# devboard_kw2xd_v2_1.net
KiCad netlist of a schematic drawn in EAGLE
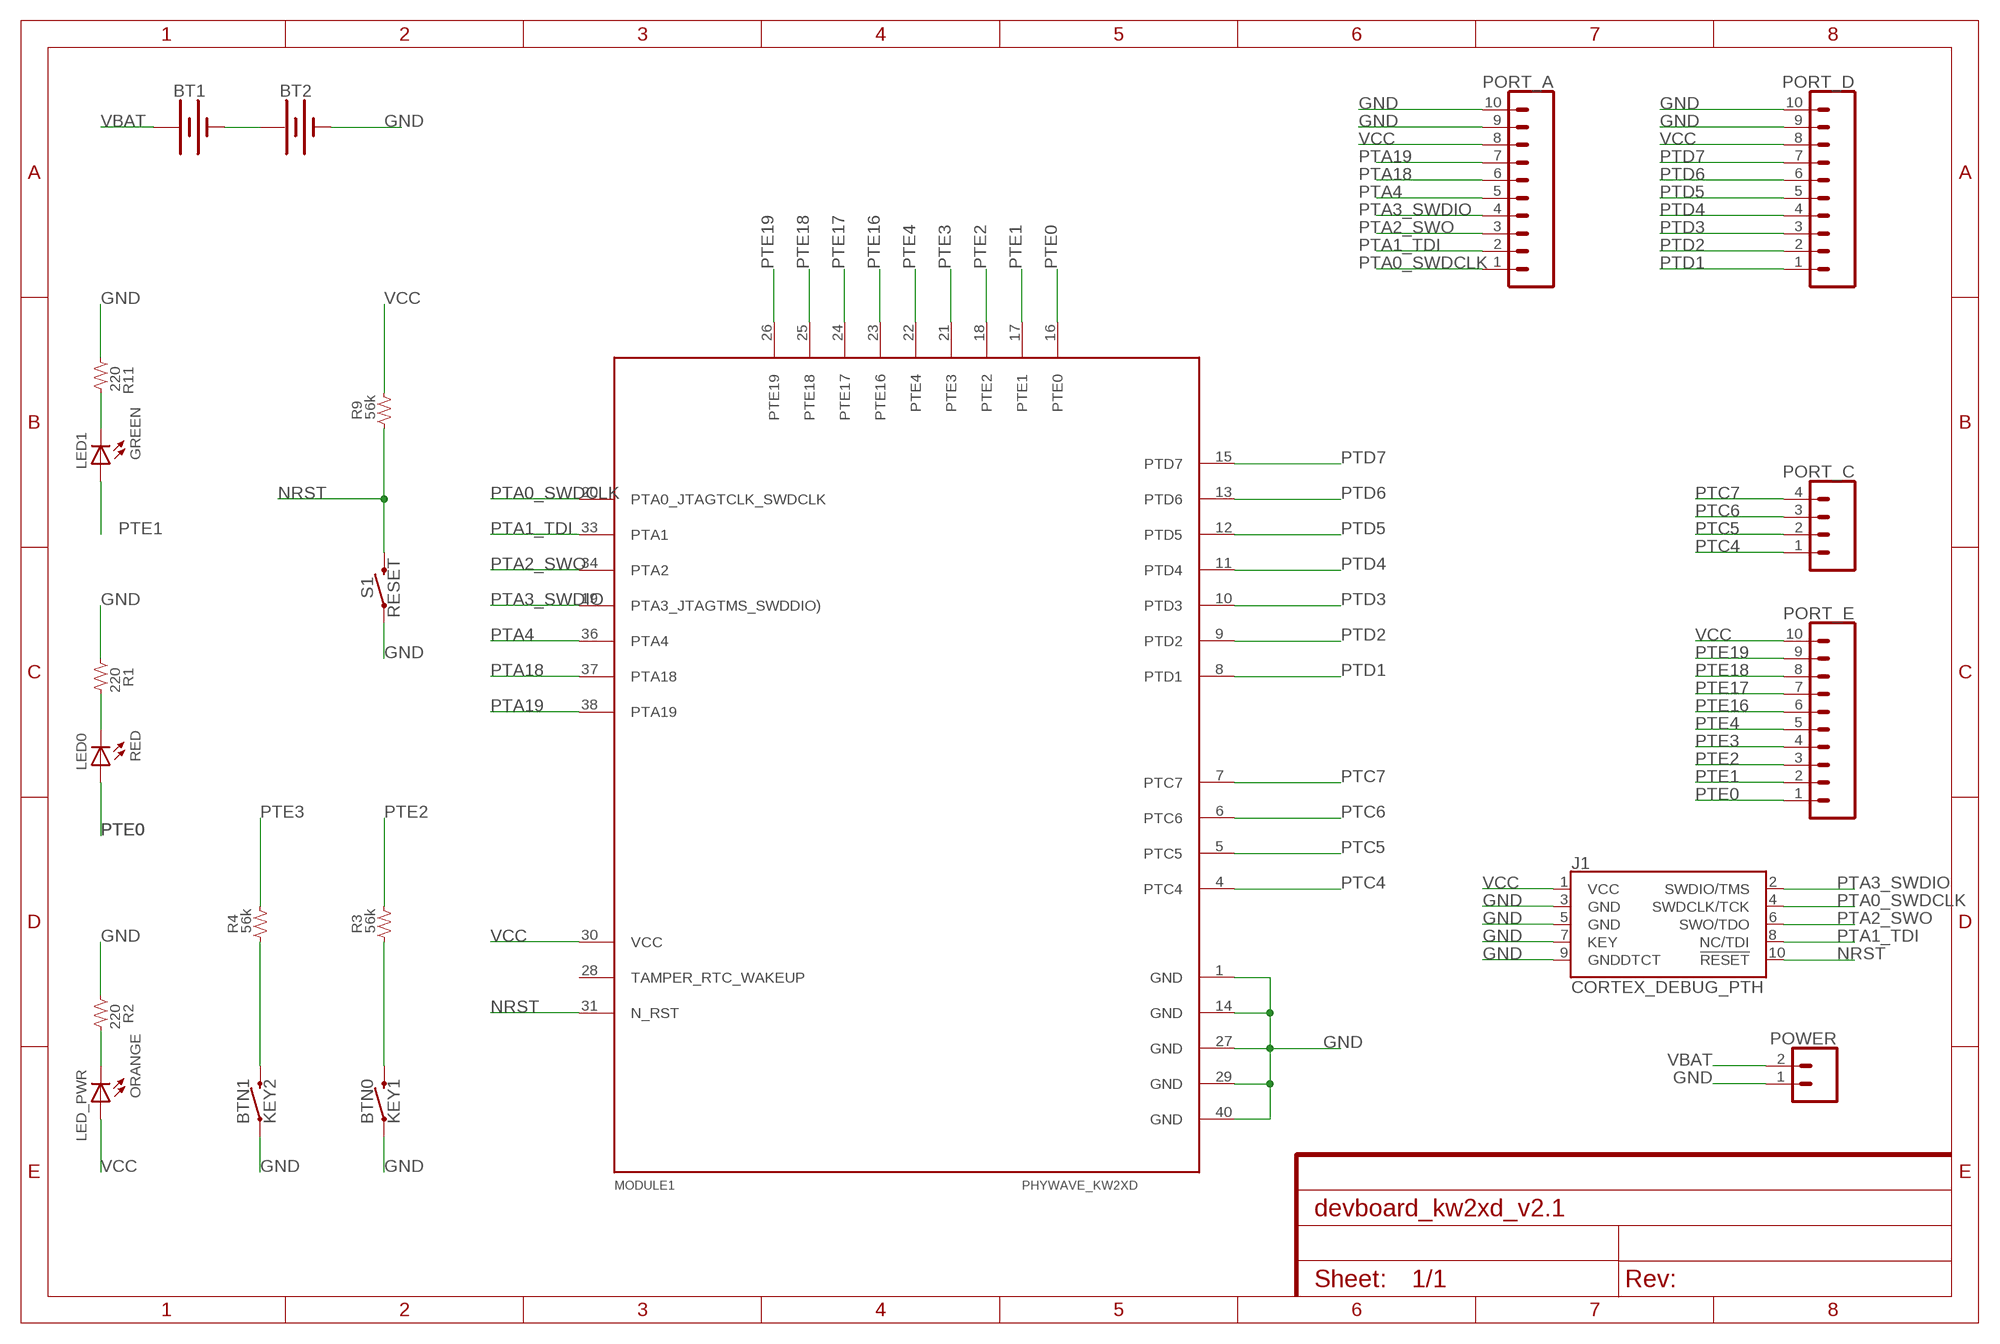
[diagram p0: schematic, sheet 1]

(export (version "E")
  (design (tool "Eeschema 10.0.6"))
  (components
    (comp (ref "BT1")
      (value "BATTERY-AAA")
      (footprint "eagle-import:BATTERY-AAA")
      (libsource (lib "eagle-import") (part "BATTERY-AAA"))
    )
    (comp (ref "BT2")
      (value "BATTERY-AAA")
      (footprint "eagle-import:BATTERY-AAA")
      (libsource (lib "eagle-import") (part "BATTERY-AAA"))
    )
    (comp (ref "BTN0")
      (value "KEY1")
      (footprint "eagle-import:TACTILE_SWITCH_SMD_4.6X2.8MM")
      (libsource (lib "eagle-import") (part "MOMENTARY-SWITCH-SPST-SMD-4.6X2.8MM"))
    )
    (comp (ref "BTN1")
      (value "KEY2")
      (footprint "eagle-import:TACTILE_SWITCH_SMD_4.6X2.8MM")
      (libsource (lib "eagle-import") (part "MOMENTARY-SWITCH-SPST-SMD-4.6X2.8MM"))
    )
    (comp (ref "J1")
      (value "CORTEX_DEBUG_PTH")
      (footprint "eagle-import:2X5-PTH-1.27MM")
      (libsource (lib "eagle-import") (part "CORTEX_DEBUG_PTH"))
    )
    (comp (ref "LED0")
      (value "RED")
      (footprint "eagle-import:LED0603")
      (libsource (lib "eagle-import") (part "LED-0603"))
    )
    (comp (ref "LED1")
      (value "GREEN")
      (footprint "eagle-import:LED0603")
      (libsource (lib "eagle-import") (part "LED-0603"))
    )
    (comp (ref "LED_PWR")
      (value "ORANGE")
      (footprint "eagle-import:LED0603")
      (libsource (lib "eagle-import") (part "LED-0603"))
    )
    (comp (ref "MODULE1")
      (value "PHYWAVE_KW2XD")
      (footprint "eagle-import:PHYWAVE_KW2XD")
      (libsource (lib "eagle-import") (part "PHYWAVE_KW2XD"))
    )
    (comp (ref "PORT_A")
      (value "CONN_10\"")
      (footprint "eagle-import:1X10")
      (libsource (lib "eagle-import") (part "CONN_10{dblquote}"))
    )
    (comp (ref "PORT_C")
      (value "CONN_04")
      (footprint "eagle-import:1X04")
      (libsource (lib "eagle-import") (part "CONN_04"))
    )
    (comp (ref "PORT_D")
      (value "CONN_10\"")
      (footprint "eagle-import:1X10")
      (libsource (lib "eagle-import") (part "CONN_10{dblquote}"))
    )
    (comp (ref "PORT_E")
      (value "CONN_10\"")
      (footprint "eagle-import:1X10")
      (libsource (lib "eagle-import") (part "CONN_10{dblquote}"))
    )
    (comp (ref "POWER")
      (value "CONN_02")
      (footprint "eagle-import:1X02")
      (libsource (lib "eagle-import") (part "CONN_02"))
    )
    (comp (ref "R1")
      (value "220")
      (footprint "eagle-import:SMD0603")
      (libsource (lib "eagle-import") (part "R-0603"))
    )
    (comp (ref "R2")
      (value "220")
      (footprint "eagle-import:SMD0603")
      (libsource (lib "eagle-import") (part "R-0603"))
    )
    (comp (ref "R3")
      (value "56k")
      (footprint "eagle-import:SMD0603")
      (libsource (lib "eagle-import") (part "R-0603"))
    )
    (comp (ref "R4")
      (value "56k")
      (footprint "eagle-import:SMD0603")
      (libsource (lib "eagle-import") (part "R-0603"))
    )
    (comp (ref "R9")
      (value "56k")
      (footprint "eagle-import:SMD0603")
      (libsource (lib "eagle-import") (part "R-0603"))
    )
    (comp (ref "R11")
      (value "220")
      (footprint "eagle-import:SMD0603")
      (libsource (lib "eagle-import") (part "R-0603"))
    )
    (comp (ref "S1")
      (value "RESET")
      (footprint "eagle-import:TACTILE_SWITCH_SMD_4.6X2.8MM")
      (libsource (lib "eagle-import") (part "MOMENTARY-SWITCH-SPST-SMD-4.6X2.8MM"))
    )
  )
  (nets
    (net (code "1") (name "/GND") (class "Default")
      (node (ref "BT2") (pin "GND@1") (pinfunction "-_GND@1") (pintype "power_in"))
      (node (ref "BTN0") (pin "1") (pinfunction "1_1") (pintype "passive"))
      (node (ref "BTN0") (pin "2") (pinfunction "1_2") (pintype "passive"))
      (node (ref "BTN1") (pin "1") (pinfunction "1_1") (pintype "passive"))
      (node (ref "BTN1") (pin "2") (pinfunction "1_2") (pintype "passive"))
      (node (ref "J1") (pin "3") (pinfunction "GND_3") (pintype "bidirectional"))
      (node (ref "J1") (pin "5") (pinfunction "GND_5") (pintype "bidirectional"))
      (node (ref "J1") (pin "7") (pinfunction "KEY_7") (pintype "bidirectional"))
      (node (ref "J1") (pin "9") (pinfunction "GNDDTCT_9") (pintype "bidirectional"))
      (node (ref "MODULE1") (pin "1") (pinfunction "GND_1") (pintype "bidirectional"))
      (node (ref "MODULE1") (pin "14") (pinfunction "GND_14") (pintype "bidirectional"))
      (node (ref "MODULE1") (pin "27") (pinfunction "GND_27") (pintype "bidirectional"))
      (node (ref "MODULE1") (pin "29") (pinfunction "GND_29") (pintype "bidirectional"))
      (node (ref "MODULE1") (pin "40") (pinfunction "GND_40") (pintype "bidirectional"))
      (node (ref "PORT_A") (pin "10") (pinfunction "10_10") (pintype "passive"))
      (node (ref "PORT_A") (pin "9") (pinfunction "9_9") (pintype "passive"))
      (node (ref "PORT_D") (pin "10") (pinfunction "10_10") (pintype "passive"))
      (node (ref "PORT_D") (pin "9") (pinfunction "9_9") (pintype "passive"))
      (node (ref "POWER") (pin "1") (pinfunction "1_1") (pintype "passive"))
      (node (ref "R1") (pin "1") (pinfunction "1_1") (pintype "passive"))
      (node (ref "R11") (pin "1") (pinfunction "1_1") (pintype "passive"))
      (node (ref "R2") (pin "1") (pinfunction "1_1") (pintype "passive"))
      (node (ref "S1") (pin "1") (pinfunction "1_1") (pintype "passive"))
      (node (ref "S1") (pin "2") (pinfunction "1_2") (pintype "passive"))
    )
    (net (code "2") (name "/NRST") (class "Default")
      (node (ref "BTN0") (pin "3") (pinfunction "2_3") (pintype "passive"))
      (node (ref "BTN0") (pin "4") (pinfunction "2_4") (pintype "passive"))
      (node (ref "J1") (pin "10") (pinfunction "~{RESET}_10") (pintype "bidirectional"))
      (node (ref "MODULE1") (pin "31") (pinfunction "N_RST_31") (pintype "bidirectional"))
      (node (ref "R3") (pin "1") (pinfunction "1_1") (pintype "passive"))
      (node (ref "R9") (pin "1") (pinfunction "1_1") (pintype "passive"))
      (node (ref "S1") (pin "3") (pinfunction "2_3") (pintype "passive"))
      (node (ref "S1") (pin "4") (pinfunction "2_4") (pintype "passive"))
    )
    (net (code "3") (name "/PTA0_SWDCLK") (class "Default")
      (node (ref "J1") (pin "4") (pinfunction "SWDCLK/TCK_4") (pintype "bidirectional"))
      (node (ref "MODULE1") (pin "20") (pinfunction "PTA0_JTAGTCLK_SWDCLK_20") (pintype "bidirectional"))
      (node (ref "PORT_A") (pin "1") (pinfunction "1_1") (pintype "passive"))
    )
    (net (code "4") (name "/PTA1_TDI") (class "Default")
      (node (ref "J1") (pin "8") (pinfunction "NC/TDI_8") (pintype "bidirectional"))
      (node (ref "MODULE1") (pin "33") (pinfunction "PTA1_33") (pintype "bidirectional"))
      (node (ref "PORT_A") (pin "2") (pinfunction "2_2") (pintype "passive"))
    )
    (net (code "5") (name "/PTA2_SWO") (class "Default")
      (node (ref "J1") (pin "6") (pinfunction "SWO/TDO_6") (pintype "bidirectional"))
      (node (ref "MODULE1") (pin "34") (pinfunction "PTA2_34") (pintype "bidirectional"))
      (node (ref "PORT_A") (pin "3") (pinfunction "3_3") (pintype "passive"))
    )
    (net (code "6") (name "/PTA3_SWDIO") (class "Default")
      (node (ref "J1") (pin "2") (pinfunction "SWDIO/TMS_2") (pintype "bidirectional"))
      (node (ref "MODULE1") (pin "19") (pinfunction "PTA3_JTAGTMS_SWDDIO)_19") (pintype "bidirectional"))
      (node (ref "PORT_A") (pin "4") (pinfunction "4_4") (pintype "passive"))
    )
    (net (code "7") (name "/PTA4") (class "Default")
      (node (ref "MODULE1") (pin "36") (pinfunction "PTA4_36") (pintype "bidirectional"))
      (node (ref "PORT_A") (pin "5") (pinfunction "5_5") (pintype "passive"))
    )
    (net (code "8") (name "/PTA18") (class "Default")
      (node (ref "MODULE1") (pin "37") (pinfunction "PTA18_37") (pintype "bidirectional"))
      (node (ref "PORT_A") (pin "6") (pinfunction "6_6") (pintype "passive"))
    )
    (net (code "9") (name "/PTA19") (class "Default")
      (node (ref "MODULE1") (pin "38") (pinfunction "PTA19_38") (pintype "bidirectional"))
      (node (ref "PORT_A") (pin "7") (pinfunction "7_7") (pintype "passive"))
    )
    (net (code "10") (name "/PTC4") (class "Default")
      (node (ref "MODULE1") (pin "4") (pinfunction "PTC4_4") (pintype "bidirectional"))
      (node (ref "PORT_C") (pin "1") (pinfunction "1_1") (pintype "passive"))
    )
    (net (code "11") (name "/PTC5") (class "Default")
      (node (ref "MODULE1") (pin "5") (pinfunction "PTC5_5") (pintype "bidirectional"))
      (node (ref "PORT_C") (pin "2") (pinfunction "2_2") (pintype "passive"))
    )
    (net (code "12") (name "/PTC6") (class "Default")
      (node (ref "MODULE1") (pin "6") (pinfunction "PTC6_6") (pintype "bidirectional"))
      (node (ref "PORT_C") (pin "3") (pinfunction "3_3") (pintype "passive"))
    )
    (net (code "13") (name "/PTC7") (class "Default")
      (node (ref "MODULE1") (pin "7") (pinfunction "PTC7_7") (pintype "bidirectional"))
      (node (ref "PORT_C") (pin "4") (pinfunction "4_4") (pintype "passive"))
    )
    (net (code "14") (name "/PTD1") (class "Default")
      (node (ref "MODULE1") (pin "8") (pinfunction "PTD1_8") (pintype "bidirectional"))
      (node (ref "PORT_D") (pin "1") (pinfunction "1_1") (pintype "passive"))
    )
    (net (code "15") (name "/PTD2") (class "Default")
      (node (ref "MODULE1") (pin "9") (pinfunction "PTD2_9") (pintype "bidirectional"))
      (node (ref "PORT_D") (pin "2") (pinfunction "2_2") (pintype "passive"))
    )
    (net (code "16") (name "/PTD3") (class "Default")
      (node (ref "MODULE1") (pin "10") (pinfunction "PTD3_10") (pintype "bidirectional"))
      (node (ref "PORT_D") (pin "3") (pinfunction "3_3") (pintype "passive"))
    )
    (net (code "17") (name "/PTD4") (class "Default")
      (node (ref "MODULE1") (pin "11") (pinfunction "PTD4_11") (pintype "bidirectional"))
      (node (ref "PORT_D") (pin "4") (pinfunction "4_4") (pintype "passive"))
    )
    (net (code "18") (name "/PTD5") (class "Default")
      (node (ref "MODULE1") (pin "12") (pinfunction "PTD5_12") (pintype "bidirectional"))
      (node (ref "PORT_D") (pin "5") (pinfunction "5_5") (pintype "passive"))
    )
    (net (code "19") (name "/PTD6") (class "Default")
      (node (ref "MODULE1") (pin "13") (pinfunction "PTD6_13") (pintype "bidirectional"))
      (node (ref "PORT_D") (pin "6") (pinfunction "6_6") (pintype "passive"))
    )
    (net (code "20") (name "/PTD7") (class "Default")
      (node (ref "MODULE1") (pin "15") (pinfunction "PTD7_15") (pintype "bidirectional"))
      (node (ref "PORT_D") (pin "7") (pinfunction "7_7") (pintype "passive"))
    )
    (net (code "21") (name "/PTE0") (class "Default")
      (node (ref "LED0") (pin "A") (pinfunction "A_A") (pintype "passive"))
      (node (ref "MODULE1") (pin "16") (pinfunction "PTE0_16") (pintype "bidirectional"))
      (node (ref "PORT_E") (pin "1") (pinfunction "1_1") (pintype "passive"))
    )
    (net (code "22") (name "/PTE1") (class "Default")
      (node (ref "LED1") (pin "A") (pinfunction "A_A") (pintype "passive"))
      (node (ref "MODULE1") (pin "17") (pinfunction "PTE1_17") (pintype "bidirectional"))
      (node (ref "PORT_E") (pin "2") (pinfunction "2_2") (pintype "passive"))
    )
    (net (code "23") (name "/PTE2") (class "Default")
      (node (ref "MODULE1") (pin "18") (pinfunction "PTE2_18") (pintype "bidirectional"))
      (node (ref "PORT_E") (pin "3") (pinfunction "3_3") (pintype "passive"))
      (node (ref "R3") (pin "2") (pinfunction "2_2") (pintype "passive"))
    )
    (net (code "24") (name "/PTE3") (class "Default")
      (node (ref "MODULE1") (pin "21") (pinfunction "PTE3_21") (pintype "bidirectional"))
      (node (ref "PORT_E") (pin "4") (pinfunction "4_4") (pintype "passive"))
      (node (ref "R4") (pin "2") (pinfunction "2_2") (pintype "passive"))
    )
    (net (code "25") (name "/PTE4") (class "Default")
      (node (ref "MODULE1") (pin "22") (pinfunction "PTE4_22") (pintype "bidirectional"))
      (node (ref "PORT_E") (pin "5") (pinfunction "5_5") (pintype "passive"))
    )
    (net (code "26") (name "/PTE16") (class "Default")
      (node (ref "MODULE1") (pin "23") (pinfunction "PTE16_23") (pintype "bidirectional"))
      (node (ref "PORT_E") (pin "6") (pinfunction "6_6") (pintype "passive"))
    )
    (net (code "27") (name "/PTE17") (class "Default")
      (node (ref "MODULE1") (pin "24") (pinfunction "PTE17_24") (pintype "bidirectional"))
      (node (ref "PORT_E") (pin "7") (pinfunction "7_7") (pintype "passive"))
    )
    (net (code "28") (name "/PTE18") (class "Default")
      (node (ref "MODULE1") (pin "25") (pinfunction "PTE18_25") (pintype "bidirectional"))
      (node (ref "PORT_E") (pin "8") (pinfunction "8_8") (pintype "passive"))
    )
    (net (code "29") (name "/PTE19") (class "Default")
      (node (ref "MODULE1") (pin "26") (pinfunction "PTE19_26") (pintype "bidirectional"))
      (node (ref "PORT_E") (pin "9") (pinfunction "9_9") (pintype "passive"))
    )
    (net (code "30") (name "/VBAT") (class "Default")
      (node (ref "BT1") (pin "PWR@1") (pinfunction "+_PWR@1") (pintype "power_in"))
      (node (ref "POWER") (pin "2") (pinfunction "2_2") (pintype "passive"))
    )
    (net (code "31") (name "/VCC") (class "Default")
      (node (ref "J1") (pin "1") (pinfunction "VCC_1") (pintype "bidirectional"))
      (node (ref "LED_PWR") (pin "A") (pinfunction "A_A") (pintype "passive"))
      (node (ref "MODULE1") (pin "30") (pinfunction "VCC_30") (pintype "bidirectional"))
      (node (ref "PORT_A") (pin "8") (pinfunction "8_8") (pintype "passive"))
      (node (ref "PORT_D") (pin "8") (pinfunction "8_8") (pintype "passive"))
      (node (ref "PORT_E") (pin "10") (pinfunction "10_10") (pintype "passive"))
      (node (ref "R9") (pin "2") (pinfunction "2_2") (pintype "passive"))
    )
    (net (code "32") (name "Net-(BT1--)") (class "Default")
      (node (ref "BT1") (pin "GND@1") (pinfunction "-_GND@1") (pintype "power_in"))
      (node (ref "BT2") (pin "PWR@1") (pinfunction "+_PWR@1") (pintype "power_in"))
    )
    (net (code "33") (name "Net-(BTN1-2-Pad3)") (class "Default")
      (node (ref "BTN1") (pin "3") (pinfunction "2_3") (pintype "passive"))
      (node (ref "BTN1") (pin "4") (pinfunction "2_4") (pintype "passive"))
      (node (ref "R4") (pin "1") (pinfunction "1_1") (pintype "passive"))
    )
    (net (code "34") (name "Net-(LED0-PadC)") (class "Default")
      (node (ref "LED0") (pin "C") (pinfunction "C_C") (pintype "passive"))
      (node (ref "R1") (pin "2") (pinfunction "2_2") (pintype "passive"))
    )
    (net (code "35") (name "Net-(LED1-PadC)") (class "Default")
      (node (ref "LED1") (pin "C") (pinfunction "C_C") (pintype "passive"))
      (node (ref "R11") (pin "2") (pinfunction "2_2") (pintype "passive"))
    )
    (net (code "36") (name "Net-(LED_PWR-PadC)") (class "Default")
      (node (ref "LED_PWR") (pin "C") (pinfunction "C_C") (pintype "passive"))
      (node (ref "R2") (pin "2") (pinfunction "2_2") (pintype "passive"))
    )
    (net (code "37") (name "unconnected-(MODULE1-TAMPER_RTC_WAKEUP-Pad28)") (class "Default")
      (node (ref "MODULE1") (pin "28") (pinfunction "TAMPER_RTC_WAKEUP_28") (pintype "bidirectional"))
    )
  )
)
